# Demo1.net
KiCad netlist of a schematic drawn in Altium Designer
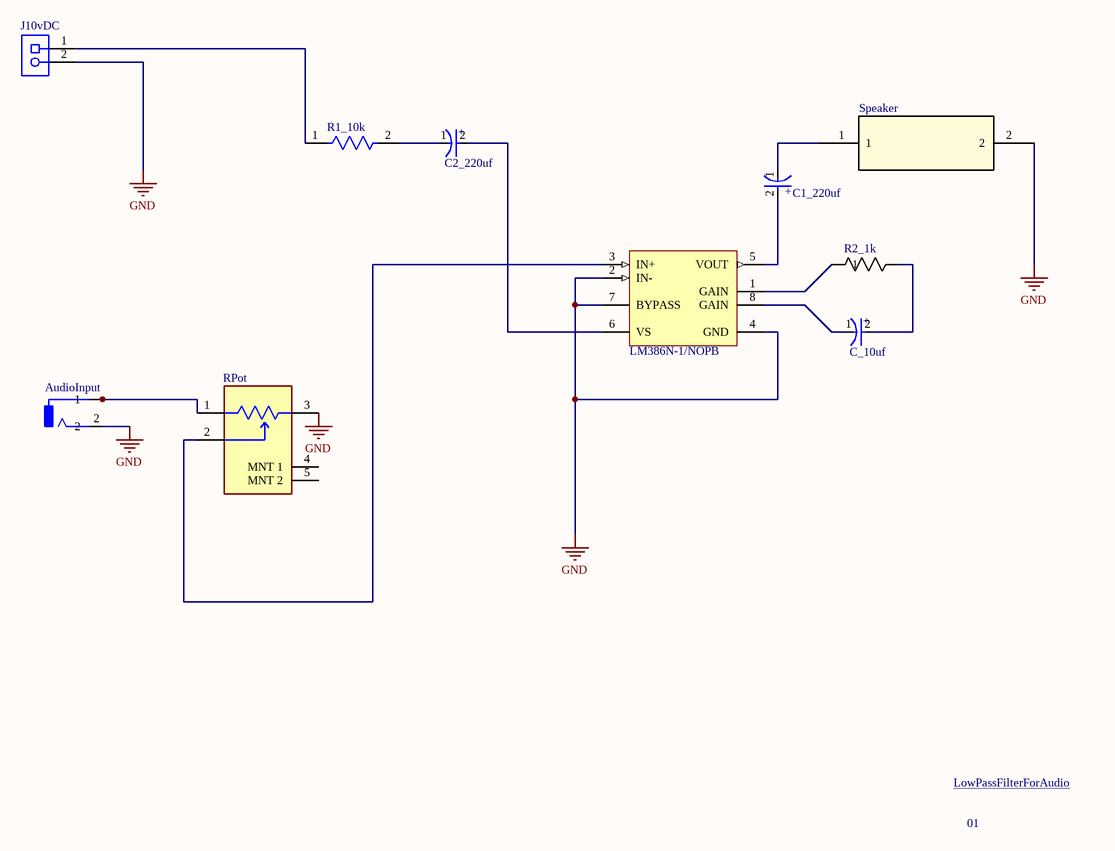
[diagram p0: Demo1.SchDoc]

(export (version "E")
  (design (tool "Eeschema 10.0.6"))
  (components
    (comp (ref "AudioInput")
      (value "RCJ-021")
      (footprint "SnapEDApcb:CUI_RCJ-021")
      (description "1 Port,  Vertical, Through Hole, Shielded, RCA Jack Connector")
      (fields (field (name "MF") "CUI Devices"))
      (libsource (lib "SnapEDAsch") (part "RCJ-021"))
    )
    (comp (ref "C1_220uf")
      (value "ECA2AHG221B")
      (footprint "FP-RAD-TH-D_12_5_0_5-L_25-MFG")
      (description "Aluminum Electrolytic Capacitors (Radial Lead Type) AEC-Q200 Qualified 220uF ±20% 100V")
      (fields (field (name "TOLERANCE") "20%"))
      (libsource (lib "Altium Content Vault") (part "203bc49f2ac43e59fd269a8c329ed05"))
    )
    (comp (ref "C2_220uf")
      (value "ECA2AHG221B")
      (footprint "FP-RAD-TH-D_12_5_0_5-L_25-MFG")
      (description "Aluminum Electrolytic Capacitors (Radial Lead Type) AEC-Q200 Qualified 220uF ±20% 100V")
      (fields (field (name "TOLERANCE") "20%"))
      (libsource (lib "Altium Content Vault") (part "203bc49f2ac43e59fd269a8c329ed05"))
    )
    (comp (ref "C_10uf")
      (value "ECA1HHG100I")
      (footprint "FP-RAD-TH-D_5_0_5-L_11_1-MFG")
      (description "Aluminum Electrolytic Capacitors (Radial Lead Type) AEC-Q200 Qualified 10uF ±20% 50V")
      (fields (field (name "TOLERANCE") "20%"))
      (libsource (lib "Altium Content Vault") (part "a00bbbee19879c290e62620ae7e47b1"))
    )
    (comp (ref "J10vDC")
      (value "1729128")
      (footprint "PHOE-1729128-2_V")
      (description "PCB Terminal Block, 13.5 A, 400 V, 2-Pin THD, RoHS, Bulk")
      (fields (field (name "MANUFACTURER") "Phoenix Contact"))
      (libsource (lib "Altium Content Vault") (part "CN-2P-F-R2"))
    )
    (comp (ref "R1_10k")
      (value "SP3AJT10R0")
      (footprint "FP-SP3A-MFG")
      (description "RES 10 OHM 5% 4W AXIAL")
      (fields (field (name "TOLERANCE") "5%"))
      (libsource (lib "Altium Content Vault") (part "1029c3af85768c4190bb7ad29bc67b5"))
    )
    (comp (ref "R2_1k")
      (value "CF14JT1K00")
      (footprint "STA_CF14_STP")
      (description "No Description Available")
      (fields (field (name "COPYRIGHT") "Copyright (C) 2022 Ultra Librarian. All rights reserved."))
      (libsource (lib "CF14JT1K00") (part "CF14JT1K00"))
    )
    (comp (ref "RPot")
      (value "PTV09A-4225F-B103")
      (footprint "FP-PTV09A-4-MFG")
      (description "POT 10K OHM 1/20W CARBON LINEAR")
      (fields (field (name "TOLERANCE") "20%"))
      (libsource (lib "Altium Content Vault") (part "705d11b747745a787204d796a5f3d12"))
    )
    (comp (ref "Speaker")
      (value "SM231508-1")
      (footprint "SPEAK_SM231508-1_DBU")
      (description "No Description Available")
      (fields (field (name "COPYRIGHT") "Copyright (C) 2022 Ultra Librarian. All rights reserved."))
      (libsource (lib "SM231508-1") (part "SM231508-1"))
    )
    (comp (ref "U1")
      (value "LM386N-1/NOPB")
      (footprint "P0008A")
      (description "Low Voltage Audio Power Amplifier, 8-pin MDIP, Pb-Free")
      (fields (field (name "MANUFACTURER") "Texas Instruments"))
      (libsource (lib "Altium Content Vault") (part "AMP-APA-LM386-8"))
    )
  )
  (nets
    (net (code "1") (name "GND") (class "Default")
      (node (ref "AudioInput") (pin "2") (pinfunction "2_2") (pintype "passive"))
      (node (ref "J10vDC") (pin "2") (pinfunction "2_2") (pintype "passive"))
      (node (ref "RPot") (pin "3") (pinfunction "3_3") (pintype "passive"))
      (node (ref "Speaker") (pin "2") (pinfunction "2_2") (pintype "passive"))
      (node (ref "U1") (pin "2") (pinfunction "IN-_2") (pintype "input"))
      (node (ref "U1") (pin "4") (pinfunction "GND_4") (pintype "power_in"))
      (node (ref "U1") (pin "7") (pinfunction "BYPASS_7") (pintype "passive"))
    )
    (net (code "2") (name "Net-(AudioInput-1-Pad1A)") (class "Default")
      (node (ref "AudioInput") (pin "1A") (pinfunction "1_1A") (pintype "passive"))
      (node (ref "AudioInput") (pin "1B") (pinfunction "1_1B") (pintype "passive"))
      (node (ref "RPot") (pin "1") (pinfunction "1_1") (pintype "passive"))
    )
    (net (code "3") (name "Net-(C1_220uf-A)") (class "Default")
      (node (ref "C1_220uf") (pin "2") (pinfunction "A_2") (pintype "passive"))
      (node (ref "U1") (pin "5") (pinfunction "VOUT_5") (pintype "output"))
    )
    (net (code "4") (name "Net-(C1_220uf-C)") (class "Default")
      (node (ref "C1_220uf") (pin "1") (pinfunction "C_1") (pintype "passive"))
      (node (ref "Speaker") (pin "1") (pinfunction "1_1") (pintype "passive"))
    )
    (net (code "5") (name "Net-(C2_220uf-A)") (class "Default")
      (node (ref "C2_220uf") (pin "2") (pinfunction "A_2") (pintype "passive"))
      (node (ref "U1") (pin "6") (pinfunction "VS_6") (pintype "power_in"))
    )
    (net (code "6") (name "Net-(C2_220uf-C)") (class "Default")
      (node (ref "C2_220uf") (pin "1") (pinfunction "C_1") (pintype "passive"))
      (node (ref "R1_10k") (pin "2") (pinfunction "2_2") (pintype "passive"))
    )
    (net (code "7") (name "Net-(C_10uf-A)") (class "Default")
      (node (ref "C_10uf") (pin "2") (pinfunction "A_2") (pintype "passive"))
      (node (ref "R2_1k") (pin "2") (pinfunction "2_2") (pintype "passive"))
    )
    (net (code "8") (name "Net-(C_10uf-C)") (class "Default")
      (node (ref "C_10uf") (pin "1") (pinfunction "C_1") (pintype "passive"))
      (node (ref "U1") (pin "8") (pinfunction "GAIN_8") (pintype "passive"))
    )
    (net (code "9") (name "Net-(J10vDC-Pad1)") (class "Default")
      (node (ref "J10vDC") (pin "1") (pinfunction "1_1") (pintype "passive"))
      (node (ref "R1_10k") (pin "1") (pinfunction "1_1") (pintype "passive"))
    )
    (net (code "10") (name "Net-(R2_1k-Pad1)") (class "Default")
      (node (ref "R2_1k") (pin "1") (pinfunction "1_1") (pintype "passive"))
      (node (ref "U1") (pin "1") (pinfunction "GAIN_1") (pintype "passive"))
    )
    (net (code "11") (name "Net-(U1-IN+)") (class "Default")
      (node (ref "RPot") (pin "2") (pinfunction "2_2") (pintype "passive"))
      (node (ref "U1") (pin "3") (pinfunction "IN+_3") (pintype "input"))
    )
    (net (code "12") (name "unconnected-(RPot-MNT_1-Pad4)") (class "Default")
      (node (ref "RPot") (pin "4") (pinfunction "MNT_1_4") (pintype "passive"))
    )
    (net (code "13") (name "unconnected-(RPot-MNT_2-Pad5)") (class "Default")
      (node (ref "RPot") (pin "5") (pinfunction "MNT_2_5") (pintype "passive"))
    )
  )
)
